# Sheet1.net
KiCad netlist of a schematic drawn in Altium Designer
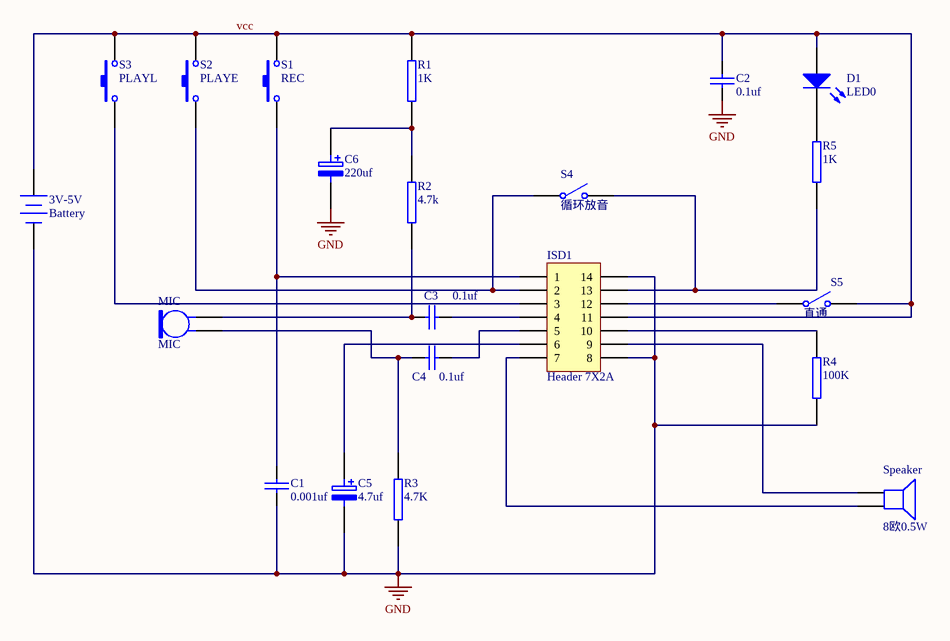
[diagram p0: Sheet1.SchDoc]

(export (version "E")
  (design (tool "Eeschema 10.0.6"))
  (components
    (comp (ref "3V-5V")
      (value "Battery")
      (footprint "BAT-2")
      (description "Multicell Battery")
      (fields (field (name "PUBLISHER") "Altium Limited"))
      (libsource (lib "Miscellaneous Devices") (part "Battery"))
    )
    (comp (ref "C1")
      (value "0.001uf")
      (footprint "RAD4")
      (description "Capacitor")
      (libsource (lib "light") (part "CAP"))
    )
    (comp (ref "C2")
      (value "0.1uf")
      (footprint "RAD4")
      (description "Capacitor")
      (libsource (lib "light") (part "CAP"))
    )
    (comp (ref "C3")
      (value "0.1uf")
      (footprint "RAD4")
      (description "Capacitor")
      (libsource (lib "light") (part "CAP"))
    )
    (comp (ref "C4")
      (value "0.1uf")
      (footprint "RAD4")
      (description "Capacitor")
      (libsource (lib "light") (part "CAP"))
    )
    (comp (ref "C5")
      (value "4.7uf")
      (footprint "RB5/8")
      (description "Electrolytic Capacitor")
      (libsource (lib "light") (part "ELECTRO2"))
    )
    (comp (ref "C6")
      (value "220uf")
      (footprint "RB5/8")
      (description "Electrolytic Capacitor")
      (libsource (lib "light") (part "ELECTRO2"))
    )
    (comp (ref "D1")
      (value "LED0")
      (footprint "LED-0")
      (description "Typical INFRARED GaAs LED")
      (fields (field (name "PUBLISHER") "Altium Limited"))
      (libsource (lib "Miscellaneous Devices") (part "LED0"))
    )
    (comp (ref "ISD1")
      (value "Header 7X2A")
      (footprint "DIP14")
      (description "Header, 7-Pin, Dual row")
      (fields (field (name "PUBLISHER") "Altium Limited"))
      (libsource (lib "light") (part "Header 7X2A"))
    )
    (comp (ref "MIC")
      (value "MIC")
      (footprint "PIN2")
      (description "Microphone")
      (fields (field (name "PUBLISHER") "Altium Limited"))
      (libsource (lib "Miscellaneous Devices") (part "Mic2"))
    )
    (comp (ref "R1") (value "1K") (footprint "AXIAL0.4") (libsource (lib "light") (part "RES2")))
    (comp (ref "R2") (value "4.7k") (footprint "AXIAL0.4") (libsource (lib "light") (part "RES2")))
    (comp (ref "R3") (value "4.7K") (footprint "AXIAL0.4") (libsource (lib "light") (part "RES2")))
    (comp (ref "R4") (value "100K") (footprint "AXIAL0.4") (libsource (lib "light") (part "RES2")))
    (comp (ref "R5") (value "1K") (footprint "AXIAL0.4") (libsource (lib "light") (part "RES2")))
    (comp (ref "S1")
      (value "REC")
      (footprint "SPST-2")
      (description "Switch")
      (fields (field (name "PUBLISHER") "Altium Limited"))
      (libsource (lib "Miscellaneous Devices") (part "SW-PB"))
    )
    (comp (ref "S2")
      (value "PLAYE")
      (footprint "SPST-2")
      (description "Switch")
      (fields (field (name "PUBLISHER") "Altium Limited"))
      (libsource (lib "Miscellaneous Devices") (part "SW-PB"))
    )
    (comp (ref "S3")
      (value "PLAYL")
      (footprint "SPST-2")
      (description "Switch")
      (fields (field (name "PUBLISHER") "Altium Limited"))
      (libsource (lib "Miscellaneous Devices") (part "SW-PB"))
    )
    (comp (ref "S4")
      (value "循环放音")
      (footprint "SPST-2")
      (description "Single-Pole, Single-Throw Switch")
      (fields (field (name "PUBLISHER") "Altium Limited"))
      (libsource (lib "Miscellaneous Devices") (part "SW-SPST"))
    )
    (comp (ref "S5")
      (value "直通")
      (footprint "SPST-2")
      (description "Single-Pole, Single-Throw Switch")
      (fields (field (name "PUBLISHER") "Altium Limited"))
      (libsource (lib "Miscellaneous Devices") (part "SW-SPST"))
    )
    (comp (ref "Speaker")
      (value "8欧0.5W")
      (footprint "PIN2")
      (description "Loudspeaker")
      (fields (field (name "PUBLISHER") "Altium Limited"))
      (libsource (lib "Miscellaneous Devices") (part "Speaker"))
    )
  )
  (nets
    (net (code "1") (name "/vcc") (class "Default")
      (node (ref "3V-5V") (pin "1") (pinfunction "+_1") (pintype "passive"))
      (node (ref "C2") (pin "1") (pinfunction "1_1") (pintype "passive"))
      (node (ref "D1") (pin "1") (pinfunction "A_1") (pintype "passive"))
      (node (ref "ISD1") (pin "11") (pinfunction "11_11") (pintype "passive"))
      (node (ref "R1") (pin "2") (pinfunction "2_2") (pintype "passive"))
      (node (ref "S1") (pin "2") (pinfunction "2_2") (pintype "passive"))
      (node (ref "S2") (pin "2") (pinfunction "2_2") (pintype "passive"))
      (node (ref "S3") (pin "2") (pinfunction "2_2") (pintype "passive"))
      (node (ref "S5") (pin "2") (pinfunction "NO_2") (pintype "passive"))
    )
    (net (code "2") (name "GND") (class "Default")
      (node (ref "3V-5V") (pin "2") (pinfunction "-_2") (pintype "passive"))
      (node (ref "C1") (pin "2") (pinfunction "2_2") (pintype "passive"))
      (node (ref "C2") (pin "2") (pinfunction "2_2") (pintype "passive"))
      (node (ref "C5") (pin "2") (pinfunction "2_2") (pintype "passive"))
      (node (ref "C6") (pin "2") (pinfunction "2_2") (pintype "passive"))
      (node (ref "ISD1") (pin "14") (pinfunction "14_14") (pintype "passive"))
      (node (ref "ISD1") (pin "8") (pinfunction "8_8") (pintype "passive"))
      (node (ref "R3") (pin "2") (pinfunction "2_2") (pintype "passive"))
      (node (ref "R4") (pin "1") (pinfunction "1_1") (pintype "passive"))
    )
    (net (code "3") (name "Net-(C1-Pad1)") (class "Default")
      (node (ref "C1") (pin "1") (pinfunction "1_1") (pintype "passive"))
      (node (ref "ISD1") (pin "1") (pinfunction "1_1") (pintype "passive"))
      (node (ref "S1") (pin "1") (pinfunction "1_1") (pintype "passive"))
    )
    (net (code "4") (name "Net-(C3-Pad1)") (class "Default")
      (node (ref "C3") (pin "1") (pinfunction "1_1") (pintype "passive"))
      (node (ref "ISD1") (pin "4") (pinfunction "4_4") (pintype "passive"))
    )
    (net (code "5") (name "Net-(C3-Pad2)") (class "Default")
      (node (ref "C3") (pin "2") (pinfunction "2_2") (pintype "passive"))
      (node (ref "MIC") (pin "2") (pinfunction "2_2") (pintype "passive"))
      (node (ref "R2") (pin "1") (pinfunction "1_1") (pintype "passive"))
    )
    (net (code "6") (name "Net-(C4-Pad1)") (class "Default")
      (node (ref "C4") (pin "1") (pinfunction "1_1") (pintype "passive"))
      (node (ref "MIC") (pin "1") (pinfunction "1_1") (pintype "passive"))
      (node (ref "R3") (pin "1") (pinfunction "1_1") (pintype "passive"))
    )
    (net (code "7") (name "Net-(C4-Pad2)") (class "Default")
      (node (ref "C4") (pin "2") (pinfunction "2_2") (pintype "passive"))
      (node (ref "ISD1") (pin "5") (pinfunction "5_5") (pintype "passive"))
    )
    (net (code "8") (name "Net-(C5-Pad1)") (class "Default")
      (node (ref "C5") (pin "1") (pinfunction "1_1") (pintype "passive"))
      (node (ref "ISD1") (pin "6") (pinfunction "6_6") (pintype "passive"))
    )
    (net (code "9") (name "Net-(C6-Pad1)") (class "Default")
      (node (ref "C6") (pin "1") (pinfunction "1_1") (pintype "passive"))
      (node (ref "R1") (pin "1") (pinfunction "1_1") (pintype "passive"))
      (node (ref "R2") (pin "2") (pinfunction "2_2") (pintype "passive"))
    )
    (net (code "10") (name "Net-(D1-K)") (class "Default")
      (node (ref "D1") (pin "2") (pinfunction "K_2") (pintype "passive"))
      (node (ref "R5") (pin "2") (pinfunction "2_2") (pintype "passive"))
    )
    (net (code "11") (name "Net-(ISD1-Pad3)") (class "Default")
      (node (ref "ISD1") (pin "3") (pinfunction "3_3") (pintype "passive"))
      (node (ref "S3") (pin "1") (pinfunction "1_1") (pintype "passive"))
    )
    (net (code "12") (name "Net-(ISD1-Pad7)") (class "Default")
      (node (ref "ISD1") (pin "7") (pinfunction "7_7") (pintype "passive"))
      (node (ref "Speaker") (pin "2") (pinfunction "2_2") (pintype "passive"))
    )
    (net (code "13") (name "Net-(ISD1-Pad9)") (class "Default")
      (node (ref "ISD1") (pin "9") (pinfunction "9_9") (pintype "passive"))
      (node (ref "Speaker") (pin "1") (pinfunction "1_1") (pintype "passive"))
    )
    (net (code "14") (name "Net-(ISD1-Pad10)") (class "Default")
      (node (ref "ISD1") (pin "10") (pinfunction "10_10") (pintype "passive"))
      (node (ref "R4") (pin "2") (pinfunction "2_2") (pintype "passive"))
    )
    (net (code "15") (name "Net-(S4-COMMON)") (class "Default")
      (node (ref "ISD1") (pin "2") (pinfunction "2_2") (pintype "passive"))
      (node (ref "S2") (pin "1") (pinfunction "1_1") (pintype "passive"))
      (node (ref "S4") (pin "1") (pinfunction "COMMON_1") (pintype "passive"))
    )
    (net (code "16") (name "Net-(S4-NO)") (class "Default")
      (node (ref "ISD1") (pin "13") (pinfunction "13_13") (pintype "passive"))
      (node (ref "R5") (pin "1") (pinfunction "1_1") (pintype "passive"))
      (node (ref "S4") (pin "2") (pinfunction "NO_2") (pintype "passive"))
    )
    (net (code "17") (name "Net-(S5-COMMON)") (class "Default")
      (node (ref "ISD1") (pin "12") (pinfunction "12_12") (pintype "passive"))
      (node (ref "S5") (pin "1") (pinfunction "COMMON_1") (pintype "passive"))
    )
  )
)
